# ETHERNET.net
KiCad netlist of a schematic drawn in Altium Designer
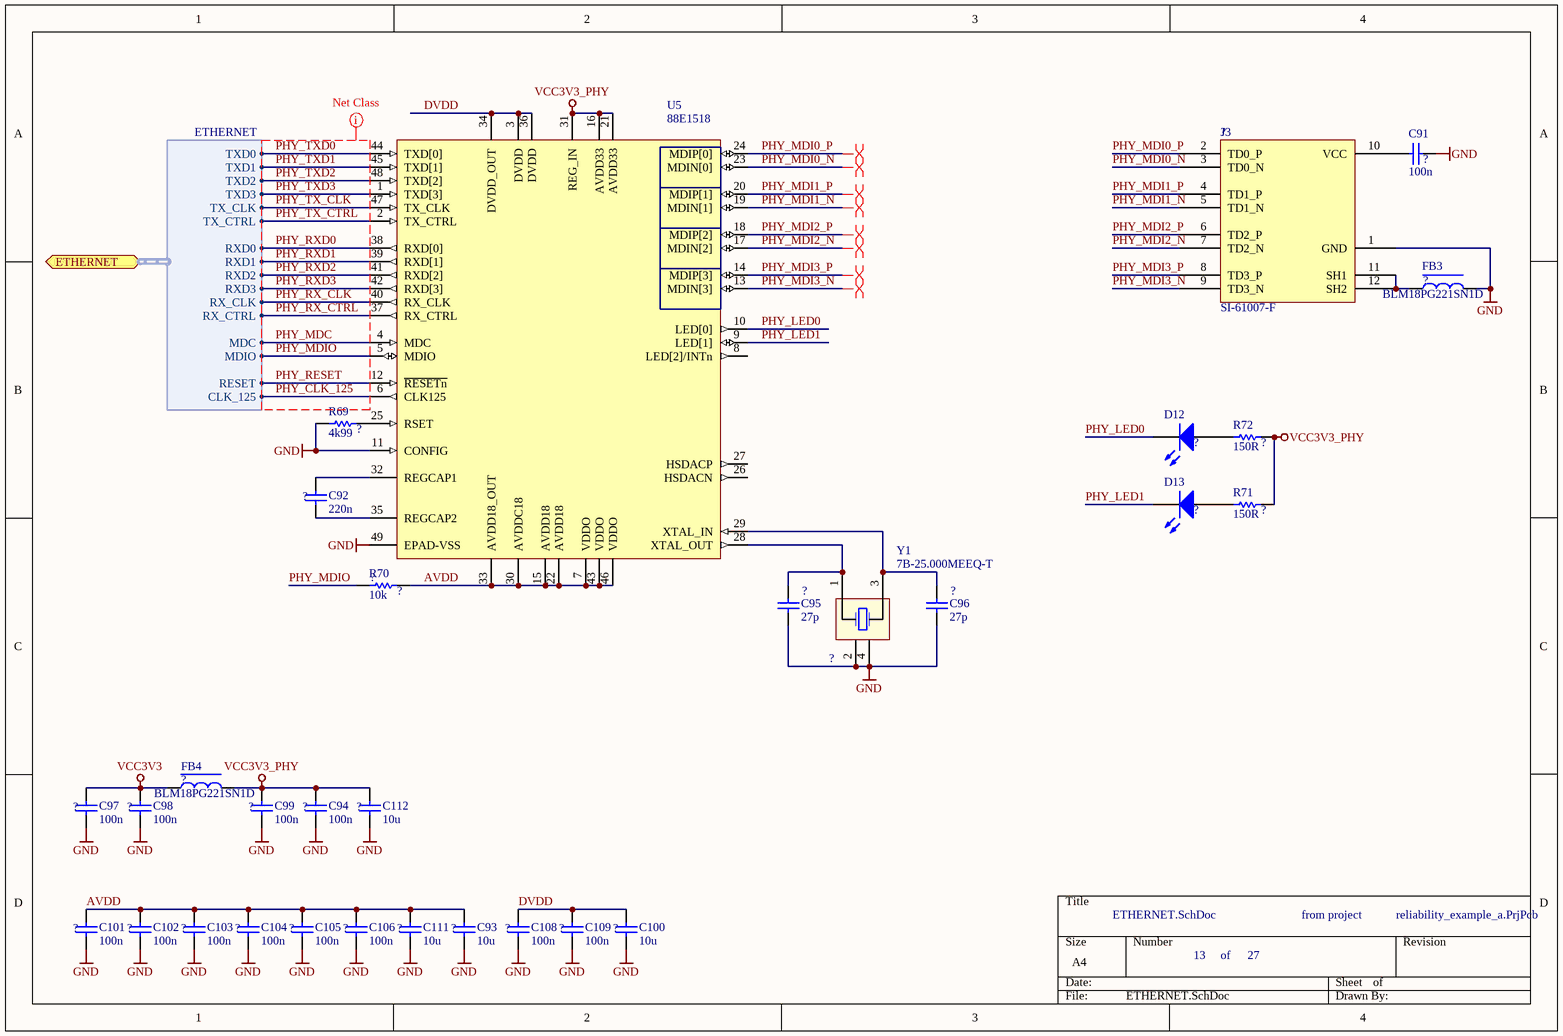
[diagram p0: ETHERNET.SchDoc]

(export (version "E")
  (design (tool "Eeschema 10.0.6"))
  (components
    (comp (ref "C91")
      (value "100n")
      (footprint "CAPC1005L")
      (description "Capacitor")
      (fields
        (field (name "MANUFACTURER") "Generic Components")
        (field (name "SN_CATEGORY") "?")
        (field (name "PUBLISHER") "Altium Hobart Technology Centre")
      )
      (libsource (lib "Miscellaneous Devices") (part "Cap"))
    )
    (comp (ref "C92")
      (value "220n")
      (footprint "CAPC1005L")
      (description "Capacitor")
      (fields
        (field (name "MANUFACTURER") "Generic Components")
        (field (name "SN_CATEGORY") "?")
        (field (name "PUBLISHER") "Altium Hobart Technology Centre")
      )
      (libsource (lib "Miscellaneous Devices") (part "Cap"))
    )
    (comp (ref "C93")
      (value "10u")
      (footprint "CAPC1005L")
      (description "Capacitor")
      (fields
        (field (name "MANUFACTURER") "Generic Components")
        (field (name "SN_CATEGORY") "?")
        (field (name "PUBLISHER") "Altium Hobart Technology Centre")
      )
      (libsource (lib "Miscellaneous Devices") (part "Cap"))
    )
    (comp (ref "C94")
      (value "100n")
      (footprint "CAPC1005L")
      (description "Capacitor")
      (fields
        (field (name "MANUFACTURER") "Generic Components")
        (field (name "SN_CATEGORY") "?")
        (field (name "PUBLISHER") "Altium Hobart Technology Centre")
      )
      (libsource (lib "Miscellaneous Devices") (part "Cap"))
    )
    (comp (ref "C95")
      (value "27p")
      (footprint "CAPC1005L")
      (description "Capacitor")
      (fields
        (field (name "MANUFACTURER") "Generic Components")
        (field (name "SN_CATEGORY") "?")
        (field (name "PUBLISHER") "Altium Hobart Technology Centre")
      )
      (libsource (lib "Miscellaneous Devices") (part "Cap"))
    )
    (comp (ref "C96")
      (value "27p")
      (footprint "CAPC1005L")
      (description "Capacitor")
      (fields
        (field (name "MANUFACTURER") "Generic Components")
        (field (name "SN_CATEGORY") "?")
        (field (name "PUBLISHER") "Altium Hobart Technology Centre")
      )
      (libsource (lib "Miscellaneous Devices") (part "Cap"))
    )
    (comp (ref "C97")
      (value "100n")
      (footprint "CAPC1005L")
      (description "Capacitor")
      (fields
        (field (name "MANUFACTURER") "Generic Components")
        (field (name "SN_CATEGORY") "?")
        (field (name "PUBLISHER") "Altium Hobart Technology Centre")
      )
      (libsource (lib "Miscellaneous Devices") (part "Cap"))
    )
    (comp (ref "C98")
      (value "100n")
      (footprint "CAPC1005L")
      (description "Capacitor")
      (fields
        (field (name "MANUFACTURER") "Generic Components")
        (field (name "SN_CATEGORY") "?")
        (field (name "PUBLISHER") "Altium Hobart Technology Centre")
      )
      (libsource (lib "Miscellaneous Devices") (part "Cap"))
    )
    (comp (ref "C99")
      (value "100n")
      (footprint "CAPC1005L")
      (description "Capacitor")
      (fields
        (field (name "MANUFACTURER") "Generic Components")
        (field (name "SN_CATEGORY") "?")
        (field (name "PUBLISHER") "Altium Hobart Technology Centre")
      )
      (libsource (lib "Miscellaneous Devices") (part "Cap"))
    )
    (comp (ref "C100")
      (value "10u")
      (footprint "CAPC1005L")
      (description "Capacitor")
      (fields
        (field (name "MANUFACTURER") "Generic Components")
        (field (name "SN_CATEGORY") "?")
        (field (name "PUBLISHER") "Altium Hobart Technology Centre")
      )
      (libsource (lib "Miscellaneous Devices") (part "Cap"))
    )
    (comp (ref "C101")
      (value "100n")
      (footprint "CAPC1005L")
      (description "Capacitor")
      (fields
        (field (name "MANUFACTURER") "Generic Components")
        (field (name "SN_CATEGORY") "?")
        (field (name "PUBLISHER") "Altium Hobart Technology Centre")
      )
      (libsource (lib "Miscellaneous Devices") (part "Cap"))
    )
    (comp (ref "C102")
      (value "100n")
      (footprint "CAPC1005L")
      (description "Capacitor")
      (fields
        (field (name "MANUFACTURER") "Generic Components")
        (field (name "SN_CATEGORY") "?")
        (field (name "PUBLISHER") "Altium Hobart Technology Centre")
      )
      (libsource (lib "Miscellaneous Devices") (part "Cap"))
    )
    (comp (ref "C103")
      (value "100n")
      (footprint "CAPC1005L")
      (description "Capacitor")
      (fields
        (field (name "MANUFACTURER") "Generic Components")
        (field (name "SN_CATEGORY") "?")
        (field (name "PUBLISHER") "Altium Hobart Technology Centre")
      )
      (libsource (lib "Miscellaneous Devices") (part "Cap"))
    )
    (comp (ref "C104")
      (value "100n")
      (footprint "CAPC1005L")
      (description "Capacitor")
      (fields
        (field (name "MANUFACTURER") "Generic Components")
        (field (name "SN_CATEGORY") "?")
        (field (name "PUBLISHER") "Altium Hobart Technology Centre")
      )
      (libsource (lib "Miscellaneous Devices") (part "Cap"))
    )
    (comp (ref "C105")
      (value "100n")
      (footprint "CAPC1005L")
      (description "Capacitor")
      (fields
        (field (name "MANUFACTURER") "Generic Components")
        (field (name "SN_CATEGORY") "?")
        (field (name "PUBLISHER") "Altium Hobart Technology Centre")
      )
      (libsource (lib "Miscellaneous Devices") (part "Cap"))
    )
    (comp (ref "C106")
      (value "100n")
      (footprint "CAPC1005L")
      (description "Capacitor")
      (fields
        (field (name "MANUFACTURER") "Generic Components")
        (field (name "SN_CATEGORY") "?")
        (field (name "PUBLISHER") "Altium Hobart Technology Centre")
      )
      (libsource (lib "Miscellaneous Devices") (part "Cap"))
    )
    (comp (ref "C108")
      (value "100n")
      (footprint "CAPC1005L")
      (description "Capacitor")
      (fields
        (field (name "MANUFACTURER") "Generic Components")
        (field (name "SN_CATEGORY") "?")
        (field (name "PUBLISHER") "Altium Hobart Technology Centre")
      )
      (libsource (lib "Miscellaneous Devices") (part "Cap"))
    )
    (comp (ref "C109")
      (value "100n")
      (footprint "CAPC1005L")
      (description "Capacitor")
      (fields
        (field (name "MANUFACTURER") "Generic Components")
        (field (name "SN_CATEGORY") "?")
        (field (name "PUBLISHER") "Altium Hobart Technology Centre")
      )
      (libsource (lib "Miscellaneous Devices") (part "Cap"))
    )
    (comp (ref "C111")
      (value "10u")
      (footprint "CAPC1005L")
      (description "Capacitor")
      (fields
        (field (name "MANUFACTURER") "Generic Components")
        (field (name "SN_CATEGORY") "?")
        (field (name "PUBLISHER") "Altium Hobart Technology Centre")
      )
      (libsource (lib "Miscellaneous Devices") (part "Cap"))
    )
    (comp (ref "C112")
      (value "10u")
      (footprint "CAPC1005L")
      (description "Capacitor")
      (fields
        (field (name "MANUFACTURER") "Generic Components")
        (field (name "SN_CATEGORY") "?")
        (field (name "PUBLISHER") "Altium Hobart Technology Centre")
      )
      (libsource (lib "Miscellaneous Devices") (part "Cap"))
    )
    (comp (ref "D12")
      (value "LED RED")
      (footprint "0603D")
      (description "Typical RED, GREEN, YELLOW, AMBER GaAs LED")
      (fields
        (field (name "MANUFACTURER") "Generic Components")
        (field (name "SN_CATEGORY") "?")
        (field (name "PUBLISHER") "Altium Hobart Technology Centre")
      )
      (libsource (lib "Miscellaneous Devices") (part "LED3"))
    )
    (comp (ref "D13")
      (value "LED RED")
      (footprint "0603D")
      (description "Typical RED, GREEN, YELLOW, AMBER GaAs LED")
      (fields
        (field (name "MANUFACTURER") "Generic Components")
        (field (name "SN_CATEGORY") "?")
        (field (name "PUBLISHER") "Altium Hobart Technology Centre")
      )
      (libsource (lib "Miscellaneous Devices") (part "LED3"))
    )
    (comp (ref "FB3")
      (value "BLM18PG221SN1D")
      (footprint "INDC1608L")
      (description "Ferrite Bead")
      (fields (field (name "SN_CATEGORY") "?"))
      (libsource (lib "Schlib1") (part "INDUCTOR2"))
    )
    (comp (ref "FB4")
      (value "BLM18PG221SN1D")
      (footprint "INDC1608L")
      (description "Ferrite Bead")
      (fields (field (name "SN_CATEGORY") "?"))
      (libsource (lib "Schlib1") (part "INDUCTOR2"))
    )
    (comp (ref "J3")
      (value "SI-61007-F")
      (footprint "HFJ11")
      (description "STEWART CONNECTOR - SI-61007-F - MAGJACK, RJ45, GIGABIT W/O LEDS")
      (fields (field (name "SN_CATEGORY") "?"))
      (libsource (lib "Cluster") (part "RJ45 GB"))
    )
    (comp (ref "R69")
      (value "4k99")
      (footprint "RESC1005L")
      (description "Resistor")
      (fields
        (field (name "MANUFACTURER") "Generic Components")
        (field (name "SN_CATEGORY") "?")
        (field (name "PUBLISHER") "Altium Hobart Technology Centre")
      )
      (libsource (lib "Miscellaneous Devices") (part "Res1"))
    )
    (comp (ref "R70")
      (value "10k")
      (footprint "RESC1005L")
      (description "Resistor")
      (fields
        (field (name "MANUFACTURER") "Generic Components")
        (field (name "SN_CATEGORY") "?")
        (field (name "PUBLISHER") "Altium Hobart Technology Centre")
      )
      (libsource (lib "Miscellaneous Devices") (part "Res1"))
    )
    (comp (ref "R71")
      (value "150R")
      (footprint "RESC1005L")
      (description "Resistor")
      (fields
        (field (name "MANUFACTURER") "Generic Components")
        (field (name "SN_CATEGORY") "?")
        (field (name "PUBLISHER") "Altium Hobart Technology Centre")
      )
      (libsource (lib "Miscellaneous Devices") (part "Res1"))
    )
    (comp (ref "R72")
      (value "150R")
      (footprint "RESC1005L")
      (description "Resistor")
      (fields
        (field (name "MANUFACTURER") "Generic Components")
        (field (name "SN_CATEGORY") "?")
        (field (name "PUBLISHER") "Altium Hobart Technology Centre")
      )
      (libsource (lib "Miscellaneous Devices") (part "Res1"))
    )
    (comp (ref "U5")
      (value "88E1518")
      (footprint "QFN50P700X700X100_HS-49N")
      (description "Gigabit Ethernet Transceiver")
      (fields (field (name "SN_CATEGORY") "?"))
      (libsource (lib "Schlib1") (part "88E1518"))
    )
    (comp (ref "Y1")
      (value "7B-25.000MEEQ-T")
      (footprint "CRYSTAL 5 x 3.2 mm (recommended)")
      (description "5 x 3.2 mm CRYSTAL  7B SERIES")
      (fields (field (name "SN_CATEGORY") "?"))
      (libsource (lib "amSCHlib_04.2012") (part "precision oscilator"))
    )
  )
  (nets
    (net (code "2") (name "/AVDD") (class "Default")
      (node (ref "C101") (pin "2") (pinfunction "2_2") (pintype "passive"))
      (node (ref "C102") (pin "2") (pinfunction "2_2") (pintype "passive"))
      (node (ref "C103") (pin "2") (pinfunction "2_2") (pintype "passive"))
      (node (ref "C104") (pin "2") (pinfunction "2_2") (pintype "passive"))
      (node (ref "C105") (pin "2") (pinfunction "2_2") (pintype "passive"))
      (node (ref "C106") (pin "2") (pinfunction "2_2") (pintype "passive"))
      (node (ref "C111") (pin "2") (pinfunction "2_2") (pintype "passive"))
      (node (ref "C93") (pin "2") (pinfunction "2_2") (pintype "passive"))
      (node (ref "R70") (pin "1") (pinfunction "1_1") (pintype "passive"))
      (node (ref "U5") (pin "15") (pinfunction "AVDD18_15") (pintype "power_in"))
      (node (ref "U5") (pin "22") (pinfunction "AVDD18_22") (pintype "power_in"))
      (node (ref "U5") (pin "30") (pinfunction "AVDDC18_30") (pintype "power_in"))
      (node (ref "U5") (pin "33") (pinfunction "AVDD18_OUT_33") (pintype "power_in"))
      (node (ref "U5") (pin "43") (pinfunction "VDDO_43") (pintype "power_in"))
      (node (ref "U5") (pin "46") (pinfunction "VDDO_46") (pintype "power_in"))
      (node (ref "U5") (pin "7") (pinfunction "VDDO_7") (pintype "power_in"))
    )
    (net (code "3") (name "/DVDD") (class "Default")
      (node (ref "C100") (pin "2") (pinfunction "2_2") (pintype "passive"))
      (node (ref "C108") (pin "2") (pinfunction "2_2") (pintype "passive"))
      (node (ref "C109") (pin "2") (pinfunction "2_2") (pintype "passive"))
      (node (ref "U5") (pin "3") (pinfunction "DVDD_3") (pintype "power_in"))
      (node (ref "U5") (pin "34") (pinfunction "DVDD_OUT_34") (pintype "power_in"))
      (node (ref "U5") (pin "36") (pinfunction "DVDD_36") (pintype "power_in"))
    )
    (net (code "4") (name "/PHY_CLK_125") (class "Default")
      (node (ref "U5") (pin "6") (pinfunction "CLK125_6") (pintype "output"))
    )
    (net (code "5") (name "/PHY_LED0") (class "Default")
      (node (ref "D12") (pin "2") (pinfunction "K_2") (pintype "passive"))
      (node (ref "U5") (pin "10") (pinfunction "LED[0]_10") (pintype "output"))
    )
    (net (code "6") (name "/PHY_LED1") (class "Default")
      (node (ref "D13") (pin "2") (pinfunction "K_2") (pintype "passive"))
      (node (ref "U5") (pin "9") (pinfunction "LED[1]_9") (pintype "bidirectional"))
    )
    (net (code "7") (name "/PHY_MDC") (class "Default")
      (node (ref "U5") (pin "4") (pinfunction "MDC_4") (pintype "input"))
    )
    (net (code "8") (name "/PHY_MDI0_N") (class "Default")
      (node (ref "J3") (pin "3") (pinfunction "TD0_N_3") (pintype "passive"))
      (node (ref "U5") (pin "23") (pinfunction "MDIN[0]_23") (pintype "bidirectional"))
    )
    (net (code "9") (name "/PHY_MDI0_P") (class "Default")
      (node (ref "J3") (pin "2") (pinfunction "TD0_P_2") (pintype "passive"))
      (node (ref "U5") (pin "24") (pinfunction "MDIP[0]_24") (pintype "bidirectional"))
    )
    (net (code "10") (name "/PHY_MDI1_N") (class "Default")
      (node (ref "J3") (pin "5") (pinfunction "TD1_N_5") (pintype "passive"))
      (node (ref "U5") (pin "19") (pinfunction "MDIN[1]_19") (pintype "bidirectional"))
    )
    (net (code "11") (name "/PHY_MDI1_P") (class "Default")
      (node (ref "J3") (pin "4") (pinfunction "TD1_P_4") (pintype "passive"))
      (node (ref "U5") (pin "20") (pinfunction "MDIP[1]_20") (pintype "bidirectional"))
    )
    (net (code "12") (name "/PHY_MDI2_N") (class "Default")
      (node (ref "J3") (pin "7") (pinfunction "TD2_N_7") (pintype "passive"))
      (node (ref "U5") (pin "17") (pinfunction "MDIN[2]_17") (pintype "bidirectional"))
    )
    (net (code "13") (name "/PHY_MDI2_P") (class "Default")
      (node (ref "J3") (pin "6") (pinfunction "TD2_P_6") (pintype "passive"))
      (node (ref "U5") (pin "18") (pinfunction "MDIP[2]_18") (pintype "bidirectional"))
    )
    (net (code "14") (name "/PHY_MDI3_N") (class "Default")
      (node (ref "J3") (pin "9") (pinfunction "TD3_N_9") (pintype "passive"))
      (node (ref "U5") (pin "13") (pinfunction "MDIN[3]_13") (pintype "bidirectional"))
    )
    (net (code "15") (name "/PHY_MDI3_P") (class "Default")
      (node (ref "J3") (pin "8") (pinfunction "TD3_P_8") (pintype "passive"))
      (node (ref "U5") (pin "14") (pinfunction "MDIP[3]_14") (pintype "bidirectional"))
    )
    (net (code "16") (name "/PHY_MDIO") (class "Default")
      (node (ref "R70") (pin "2") (pinfunction "2_2") (pintype "passive"))
      (node (ref "U5") (pin "5") (pinfunction "MDIO_5") (pintype "bidirectional"))
    )
    (net (code "17") (name "/PHY_RESET") (class "Default")
      (node (ref "U5") (pin "12") (pinfunction "RESETn_12") (pintype "input"))
    )
    (net (code "18") (name "/PHY_RXD0") (class "Default")
      (node (ref "U5") (pin "38") (pinfunction "RXD[0]_38") (pintype "output"))
    )
    (net (code "19") (name "/PHY_RXD1") (class "Default")
      (node (ref "U5") (pin "39") (pinfunction "RXD[1]_39") (pintype "output"))
    )
    (net (code "20") (name "/PHY_RXD2") (class "Default")
      (node (ref "U5") (pin "41") (pinfunction "RXD[2]_41") (pintype "output"))
    )
    (net (code "21") (name "/PHY_RXD3") (class "Default")
      (node (ref "U5") (pin "42") (pinfunction "RXD[3]_42") (pintype "output"))
    )
    (net (code "22") (name "/PHY_RX_CLK") (class "Default")
      (node (ref "U5") (pin "40") (pinfunction "RX_CLK_40") (pintype "output"))
    )
    (net (code "23") (name "/PHY_RX_CTRL") (class "Default")
      (node (ref "U5") (pin "37") (pinfunction "RX_CTRL_37") (pintype "output"))
    )
    (net (code "24") (name "/PHY_TXD0") (class "Default")
      (node (ref "U5") (pin "44") (pinfunction "TXD[0]_44") (pintype "input"))
    )
    (net (code "25") (name "/PHY_TXD1") (class "Default")
      (node (ref "U5") (pin "45") (pinfunction "TXD[1]_45") (pintype "input"))
    )
    (net (code "26") (name "/PHY_TXD2") (class "Default")
      (node (ref "U5") (pin "48") (pinfunction "TXD[2]_48") (pintype "input"))
    )
    (net (code "27") (name "/PHY_TXD3") (class "Default")
      (node (ref "U5") (pin "1") (pinfunction "TXD[3]_1") (pintype "input"))
    )
    (net (code "28") (name "/PHY_TX_CLK") (class "Default")
      (node (ref "U5") (pin "47") (pinfunction "TX_CLK_47") (pintype "input"))
    )
    (net (code "29") (name "/PHY_TX_CTRL") (class "Default")
      (node (ref "U5") (pin "2") (pinfunction "TX_CTRL_2") (pintype "input"))
    )
    (net (code "31") (name "GND") (class "Default")
      (node (ref "C100") (pin "1") (pinfunction "1_1") (pintype "passive"))
      (node (ref "C101") (pin "1") (pinfunction "1_1") (pintype "passive"))
      (node (ref "C102") (pin "1") (pinfunction "1_1") (pintype "passive"))
      (node (ref "C103") (pin "1") (pinfunction "1_1") (pintype "passive"))
      (node (ref "C104") (pin "1") (pinfunction "1_1") (pintype "passive"))
      (node (ref "C105") (pin "1") (pinfunction "1_1") (pintype "passive"))
      (node (ref "C106") (pin "1") (pinfunction "1_1") (pintype "passive"))
      (node (ref "C108") (pin "1") (pinfunction "1_1") (pintype "passive"))
      (node (ref "C109") (pin "1") (pinfunction "1_1") (pintype "passive"))
      (node (ref "C111") (pin "1") (pinfunction "1_1") (pintype "passive"))
      (node (ref "C112") (pin "1") (pinfunction "1_1") (pintype "passive"))
      (node (ref "C91") (pin "1") (pinfunction "1_1") (pintype "passive"))
      (node (ref "C93") (pin "1") (pinfunction "1_1") (pintype "passive"))
      (node (ref "C94") (pin "1") (pinfunction "1_1") (pintype "passive"))
      (node (ref "C95") (pin "2") (pinfunction "2_2") (pintype "passive"))
      (node (ref "C96") (pin "2") (pinfunction "2_2") (pintype "passive"))
      (node (ref "C97") (pin "1") (pinfunction "1_1") (pintype "passive"))
      (node (ref "C98") (pin "1") (pinfunction "1_1") (pintype "passive"))
      (node (ref "C99") (pin "1") (pinfunction "1_1") (pintype "passive"))
      (node (ref "FB3") (pin "2") (pintype "passive"))
      (node (ref "J3") (pin "1") (pinfunction "GND_1") (pintype "passive"))
      (node (ref "R69") (pin "2") (pinfunction "2_2") (pintype "passive"))
      (node (ref "U5") (pin "11") (pinfunction "CONFIG_11") (pintype "input"))
      (node (ref "U5") (pin "49") (pinfunction "EPAD-VSS_49") (pintype "power_in"))
      (node (ref "Y1") (pin "2") (pinfunction "GND_2") (pintype "passive"))
      (node (ref "Y1") (pin "4") (pinfunction "GND_4") (pintype "passive"))
    )
    (net (code "32") (name "Net-(D12-A)") (class "Default")
      (node (ref "D12") (pin "1") (pinfunction "A_1") (pintype "passive"))
      (node (ref "R72") (pin "2") (pinfunction "2_2") (pintype "passive"))
    )
    (net (code "33") (name "Net-(D13-A)") (class "Default")
      (node (ref "D13") (pin "1") (pinfunction "A_1") (pintype "passive"))
      (node (ref "R71") (pin "2") (pinfunction "2_2") (pintype "passive"))
    )
    (net (code "34") (name "Net-(J3-SH1)") (class "Default")
      (node (ref "FB3") (pin "1") (pintype "passive"))
      (node (ref "J3") (pin "11") (pinfunction "SH1_11") (pintype "passive"))
      (node (ref "J3") (pin "12") (pinfunction "SH2_12") (pintype "passive"))
    )
    (net (code "35") (name "Net-(J3-VCC)") (class "Default")
      (node (ref "C91") (pin "2") (pinfunction "2_2") (pintype "passive"))
      (node (ref "J3") (pin "10") (pinfunction "VCC_10") (pintype "passive"))
    )
    (net (code "36") (name "Net-(U5-REGCAP1)") (class "Default")
      (node (ref "C92") (pin "2") (pinfunction "2_2") (pintype "passive"))
      (node (ref "U5") (pin "32") (pinfunction "REGCAP1_32") (pintype "passive"))
    )
    (net (code "37") (name "Net-(U5-REGCAP2)") (class "Default")
      (node (ref "C92") (pin "1") (pinfunction "1_1") (pintype "passive"))
      (node (ref "U5") (pin "35") (pinfunction "REGCAP2_35") (pintype "power_in"))
    )
    (net (code "38") (name "Net-(U5-RSET)") (class "Default")
      (node (ref "R69") (pin "1") (pinfunction "1_1") (pintype "passive"))
      (node (ref "U5") (pin "25") (pinfunction "RSET_25") (pintype "input"))
    )
    (net (code "39") (name "Net-(U5-XTAL_IN)") (class "Default")
      (node (ref "C96") (pin "1") (pinfunction "1_1") (pintype "passive"))
      (node (ref "U5") (pin "29") (pinfunction "XTAL_IN_29") (pintype "input"))
      (node (ref "Y1") (pin "3") (pintype "passive"))
    )
    (net (code "40") (name "Net-(U5-XTAL_OUT)") (class "Default")
      (node (ref "C95") (pin "1") (pinfunction "1_1") (pintype "passive"))
      (node (ref "U5") (pin "28") (pinfunction "XTAL_OUT_28") (pintype "output"))
      (node (ref "Y1") (pin "1") (pintype "passive"))
    )
    (net (code "41") (name "VCC3V3") (class "Default")
      (node (ref "C97") (pin "2") (pinfunction "2_2") (pintype "passive"))
      (node (ref "C98") (pin "2") (pinfunction "2_2") (pintype "passive"))
      (node (ref "FB4") (pin "1") (pintype "passive"))
    )
    (net (code "42") (name "VCC3V3_PHY") (class "Default")
      (node (ref "C112") (pin "2") (pinfunction "2_2") (pintype "passive"))
      (node (ref "C94") (pin "2") (pinfunction "2_2") (pintype "passive"))
      (node (ref "C99") (pin "2") (pinfunction "2_2") (pintype "passive"))
      (node (ref "FB4") (pin "2") (pintype "passive"))
      (node (ref "R71") (pin "1") (pinfunction "1_1") (pintype "passive"))
      (node (ref "R72") (pin "1") (pinfunction "1_1") (pintype "passive"))
      (node (ref "U5") (pin "16") (pinfunction "AVDD33_16") (pintype "power_in"))
      (node (ref "U5") (pin "21") (pinfunction "AVDD33_21") (pintype "power_in"))
      (node (ref "U5") (pin "31") (pinfunction "REG_IN_31") (pintype "power_in"))
    )
    (net (code "43") (name "unconnected-(U5-HSDACN-Pad26)") (class "Default")
      (node (ref "U5") (pin "26") (pinfunction "HSDACN_26") (pintype "output"))
    )
    (net (code "44") (name "unconnected-(U5-HSDACP-Pad27)") (class "Default")
      (node (ref "U5") (pin "27") (pinfunction "HSDACP_27") (pintype "output"))
    )
    (net (code "45") (name "unconnected-(U5-LED[2]{slash}INTn-Pad8)") (class "Default")
      (node (ref "U5") (pin "8") (pinfunction "LED[2]/INTn_8") (pintype "output"))
    )
  )
)
